# PORTS.net
KiCad netlist of a schematic drawn in Altium Designer
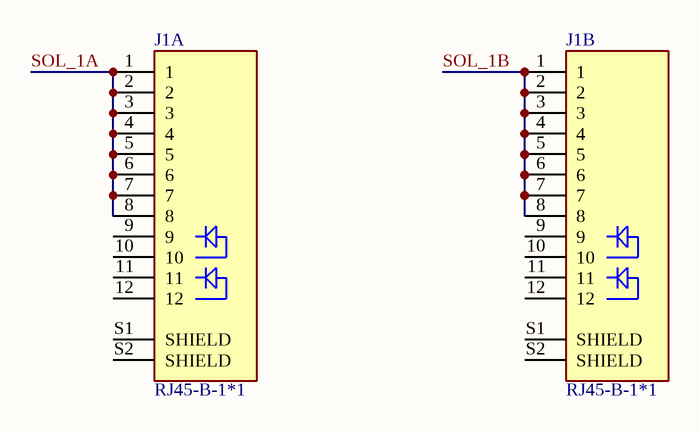
[diagram p0: PORTS.SchDoc]

(export (version "E")
  (design (tool "Eeschema 10.0.6"))
  (components
    (comp (ref "J1A")
      (value "RJ45-B-1*1")
      (footprint "TE_2-406549-1")
      (description "J - JACK - ETHERNET - Right - THT")
      (fields (field (name "LCSC PART #") "C138392"))
      (libsource (lib "JLC_PCB") (part "RJ45-B-1*1"))
    )
    (comp (ref "J1B")
      (value "RJ45-B-1*1")
      (footprint "TE_2-406549-1")
      (description "J - JACK - ETHERNET - Right - THT")
      (fields (field (name "LCSC PART #") "C138392"))
      (libsource (lib "JLC_PCB") (part "RJ45-B-1*1"))
    )
  )
  (nets
    (net (code "1") (name "/SOL_1A") (class "Default")
      (node (ref "J1A") (pin "1") (pinfunction "1_1") (pintype "passive"))
      (node (ref "J1A") (pin "2") (pinfunction "2_2") (pintype "passive"))
      (node (ref "J1A") (pin "3") (pinfunction "3_3") (pintype "passive"))
      (node (ref "J1A") (pin "4") (pinfunction "4_4") (pintype "passive"))
      (node (ref "J1A") (pin "5") (pinfunction "5_5") (pintype "passive"))
      (node (ref "J1A") (pin "6") (pinfunction "6_6") (pintype "passive"))
      (node (ref "J1A") (pin "7") (pinfunction "7_7") (pintype "passive"))
      (node (ref "J1A") (pin "8") (pinfunction "8_8") (pintype "passive"))
    )
    (net (code "2") (name "/SOL_1B") (class "Default")
      (node (ref "J1B") (pin "1") (pinfunction "1_1") (pintype "passive"))
      (node (ref "J1B") (pin "2") (pinfunction "2_2") (pintype "passive"))
      (node (ref "J1B") (pin "3") (pinfunction "3_3") (pintype "passive"))
      (node (ref "J1B") (pin "4") (pinfunction "4_4") (pintype "passive"))
      (node (ref "J1B") (pin "5") (pinfunction "5_5") (pintype "passive"))
      (node (ref "J1B") (pin "6") (pinfunction "6_6") (pintype "passive"))
      (node (ref "J1B") (pin "7") (pinfunction "7_7") (pintype "passive"))
      (node (ref "J1B") (pin "8") (pinfunction "8_8") (pintype "passive"))
    )
    (net (code "3") (name "unconnected-(J1A-Pad9)") (class "Default")
      (node (ref "J1A") (pin "9") (pinfunction "9_9") (pintype "passive"))
    )
    (net (code "4") (name "unconnected-(J1A-Pad10)") (class "Default")
      (node (ref "J1A") (pin "10") (pinfunction "10_10") (pintype "passive"))
    )
    (net (code "5") (name "unconnected-(J1A-Pad11)") (class "Default")
      (node (ref "J1A") (pin "11") (pinfunction "11_11") (pintype "passive"))
    )
    (net (code "6") (name "unconnected-(J1A-Pad12)") (class "Default")
      (node (ref "J1A") (pin "12") (pinfunction "12_12") (pintype "passive"))
    )
    (net (code "7") (name "unconnected-(J1A-SHIELD-PadS1)") (class "Default")
      (node (ref "J1A") (pin "S1") (pinfunction "SHIELD_S1") (pintype "passive"))
    )
    (net (code "8") (name "unconnected-(J1A-SHIELD-PadS2)") (class "Default")
      (node (ref "J1A") (pin "S2") (pinfunction "SHIELD_S2") (pintype "passive"))
    )
    (net (code "9") (name "unconnected-(J1B-Pad9)") (class "Default")
      (node (ref "J1B") (pin "9") (pinfunction "9_9") (pintype "passive"))
    )
    (net (code "10") (name "unconnected-(J1B-Pad10)") (class "Default")
      (node (ref "J1B") (pin "10") (pinfunction "10_10") (pintype "passive"))
    )
    (net (code "11") (name "unconnected-(J1B-Pad11)") (class "Default")
      (node (ref "J1B") (pin "11") (pinfunction "11_11") (pintype "passive"))
    )
    (net (code "12") (name "unconnected-(J1B-Pad12)") (class "Default")
      (node (ref "J1B") (pin "12") (pinfunction "12_12") (pintype "passive"))
    )
    (net (code "13") (name "unconnected-(J1B-SHIELD-PadS1)") (class "Default")
      (node (ref "J1B") (pin "S1") (pinfunction "SHIELD_S1") (pintype "passive"))
    )
    (net (code "14") (name "unconnected-(J1B-SHIELD-PadS2)") (class "Default")
      (node (ref "J1B") (pin "S2") (pinfunction "SHIELD_S2") (pintype "passive"))
    )
  )
)
